# clock.net
KiCad netlist of a schematic drawn in EAGLE
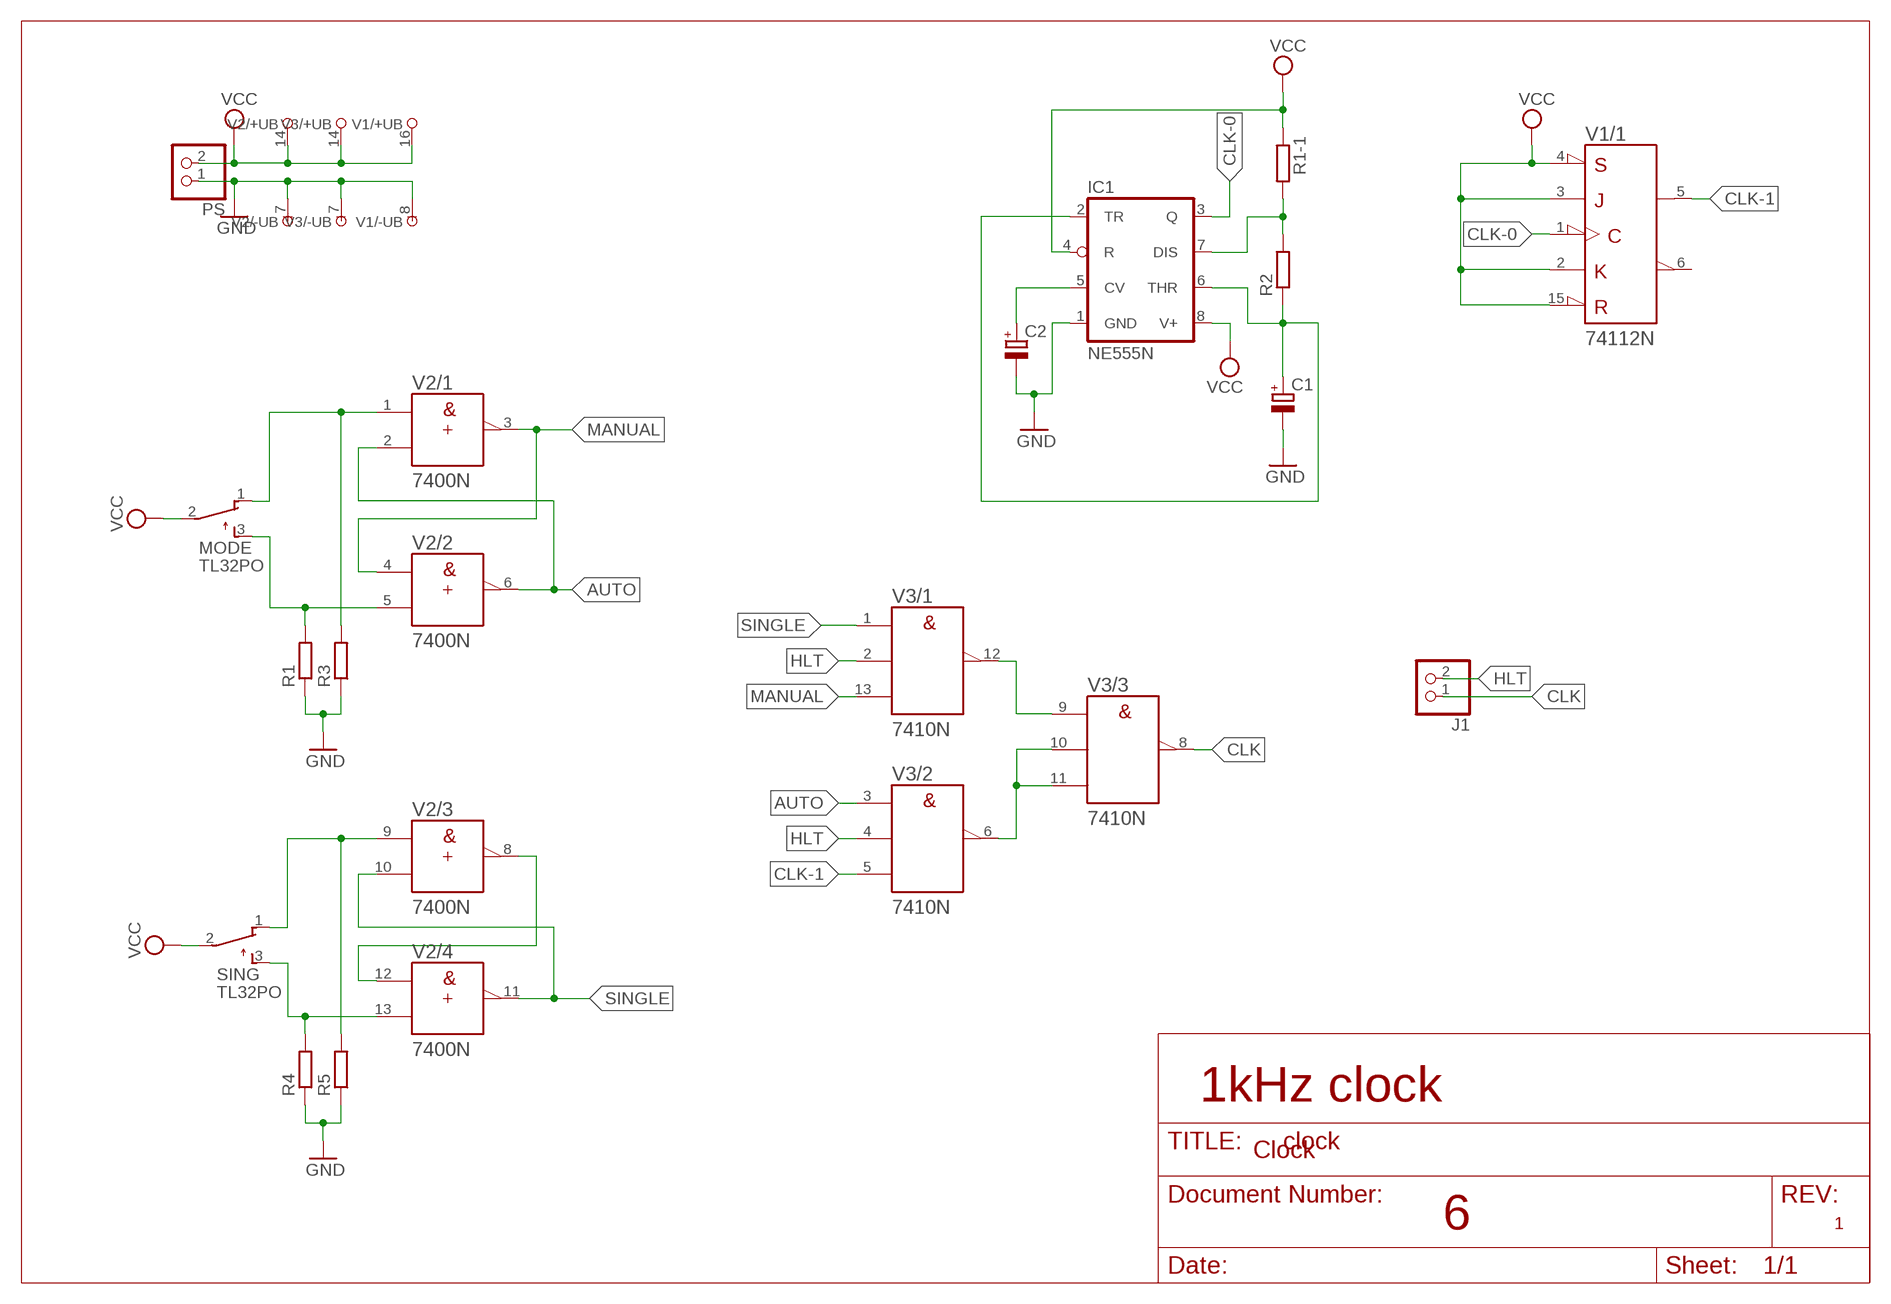
[diagram p0: schematic, sheet 1]

(export (version "E")
  (design (tool "Eeschema 10.0.6"))
  (components
    (comp (ref "C1")
      (value "CPOL-EUE2.5-6")
      (footprint "eagle-import:E2,5-6")
      (libsource (lib "eagle-import") (part "CPOL-EUE2.5-6"))
    )
    (comp (ref "C2")
      (value "CPOL-EUE2.5-6")
      (footprint "eagle-import:E2,5-6")
      (libsource (lib "eagle-import") (part "CPOL-EUE2.5-6"))
    )
    (comp (ref "IC1")
      (value "NE555N")
      (footprint "eagle-import:DIL08")
      (libsource (lib "eagle-import") (part "555NNE"))
    )
    (comp (ref "J1")
      (value "PINHD-1X2")
      (footprint "eagle-import:1X02")
      (libsource (lib "eagle-import") (part "PINHD-1X2"))
    )
    (comp (ref "MODE")
      (value "TL32PO")
      (footprint "eagle-import:TL3XPO")
      (libsource (lib "eagle-import") (part "TL32PO"))
    )
    (comp (ref "PS")
      (value "PINHD-1X2")
      (footprint "eagle-import:1X02")
      (libsource (lib "eagle-import") (part "PINHD-1X2"))
    )
    (comp (ref "R1")
      (value "R-EU_0204/7")
      (footprint "eagle-import:0204_7")
      (libsource (lib "eagle-import") (part "R-EU_0204/7"))
    )
    (comp (ref "R1-1")
      (value "R-EU_0207/10")
      (footprint "eagle-import:0207_10")
      (libsource (lib "eagle-import") (part "R-EU_0207/10"))
    )
    (comp (ref "R2")
      (value "R-EU_0207/10")
      (footprint "eagle-import:0207_10")
      (libsource (lib "eagle-import") (part "R-EU_0207/10"))
    )
    (comp (ref "R3")
      (value "R-EU_0204/7")
      (footprint "eagle-import:0204_7")
      (libsource (lib "eagle-import") (part "R-EU_0204/7"))
    )
    (comp (ref "R4")
      (value "R-EU_0204/7")
      (footprint "eagle-import:0204_7")
      (libsource (lib "eagle-import") (part "R-EU_0204/7"))
    )
    (comp (ref "R5")
      (value "R-EU_0204/7")
      (footprint "eagle-import:0204_7")
      (libsource (lib "eagle-import") (part "R-EU_0204/7"))
    )
    (comp (ref "SING")
      (value "TL32PO")
      (footprint "eagle-import:TL3XPO")
      (libsource (lib "eagle-import") (part "TL32PO"))
    )
    (comp (ref "V1")
      (value "74112N")
      (footprint "eagle-import:DIL16")
      (libsource (lib "eagle-import") (part "74112N"))
    )
    (comp (ref "V2")
      (value "7400N")
      (footprint "eagle-import:DIL14")
      (libsource (lib "eagle-import") (part "7400N"))
    )
    (comp (ref "V3")
      (value "7410N")
      (footprint "eagle-import:DIL14")
      (libsource (lib "eagle-import") (part "7410N"))
    )
  )
  (nets
    (net (code "1") (name "AUTO") (class "Default")
      (node (ref "V2") (pin "2") (pinfunction "B_2") (pintype "input"))
      (node (ref "V2") (pin "6") (pinfunction "Y_6") (pintype "output"))
      (node (ref "V3") (pin "3") (pinfunction "A_3") (pintype "input"))
    )
    (net (code "2") (name "CLK") (class "Default")
      (node (ref "J1") (pin "1") (pinfunction "1_1") (pintype "passive"))
      (node (ref "V3") (pin "8") (pinfunction "Y_8") (pintype "output"))
    )
    (net (code "3") (name "CLK-0") (class "Default")
      (node (ref "IC1") (pin "3") (pinfunction "Q_3") (pintype "output"))
      (node (ref "V1") (pin "1") (pinfunction "CLK_1") (pintype "input"))
    )
    (net (code "4") (name "CLK-1") (class "Default")
      (node (ref "V1") (pin "5") (pinfunction "Q_5") (pintype "output"))
      (node (ref "V3") (pin "5") (pinfunction "C_5") (pintype "input"))
    )
    (net (code "5") (name "GND") (class "Default")
      (node (ref "C1") (pin "-") (pinfunction "-_-") (pintype "passive"))
      (node (ref "C2") (pin "-") (pinfunction "-_-") (pintype "passive"))
      (node (ref "IC1") (pin "1") (pinfunction "GND_1") (pintype "power_in"))
      (node (ref "PS") (pin "1") (pinfunction "1_1") (pintype "passive"))
      (node (ref "R1") (pin "1") (pinfunction "1_1") (pintype "passive"))
      (node (ref "R3") (pin "1") (pinfunction "1_1") (pintype "passive"))
      (node (ref "R4") (pin "1") (pinfunction "1_1") (pintype "passive"))
      (node (ref "R5") (pin "1") (pinfunction "1_1") (pintype "passive"))
      (node (ref "V1") (pin "8") (pinfunction "-UB_8") (pintype "power_in"))
      (node (ref "V2") (pin "7") (pinfunction "-UB_7") (pintype "power_in"))
      (node (ref "V3") (pin "7") (pinfunction "-UB_7") (pintype "power_in"))
    )
    (net (code "6") (name "HLT") (class "Default")
      (node (ref "J1") (pin "2") (pinfunction "2_2") (pintype "passive"))
      (node (ref "V3") (pin "2") (pinfunction "B_2") (pintype "input"))
      (node (ref "V3") (pin "4") (pinfunction "B_4") (pintype "input"))
    )
    (net (code "7") (name "MANUAL") (class "Default")
      (node (ref "V2") (pin "3") (pinfunction "Y_3") (pintype "output"))
      (node (ref "V2") (pin "4") (pinfunction "A_4") (pintype "input"))
      (node (ref "V3") (pin "13") (pinfunction "C_13") (pintype "input"))
    )
    (net (code "8") (name "Net-(IC1-CV)") (class "Default")
      (node (ref "C2") (pin "+") (pinfunction "+_+") (pintype "passive"))
      (node (ref "IC1") (pin "5") (pinfunction "CV_5") (pintype "input"))
    )
    (net (code "9") (name "Net-(IC1-DIS)") (class "Default")
      (node (ref "IC1") (pin "7") (pinfunction "DIS_7") (pintype "input"))
      (node (ref "R1-1") (pin "2") (pinfunction "2_2") (pintype "passive"))
      (node (ref "R2") (pin "2") (pinfunction "2_2") (pintype "passive"))
    )
    (net (code "10") (name "Net-(IC1-THR)") (class "Default")
      (node (ref "C1") (pin "+") (pinfunction "+_+") (pintype "passive"))
      (node (ref "IC1") (pin "2") (pinfunction "TR_2") (pintype "input"))
      (node (ref "IC1") (pin "6") (pinfunction "THR_6") (pintype "input"))
      (node (ref "R2") (pin "1") (pinfunction "1_1") (pintype "passive"))
    )
    (net (code "11") (name "Net-(MODE-O)") (class "Default")
      (node (ref "MODE") (pin "1") (pinfunction "O_1") (pintype "passive"))
      (node (ref "R3") (pin "2") (pinfunction "2_2") (pintype "passive"))
      (node (ref "V2") (pin "1") (pinfunction "A_1") (pintype "input"))
    )
    (net (code "12") (name "Net-(MODE-S)") (class "Default")
      (node (ref "MODE") (pin "3") (pinfunction "S_3") (pintype "passive"))
      (node (ref "R1") (pin "2") (pinfunction "2_2") (pintype "passive"))
      (node (ref "V2") (pin "5") (pinfunction "B_5") (pintype "input"))
    )
    (net (code "13") (name "Net-(SING-O)") (class "Default")
      (node (ref "R5") (pin "2") (pinfunction "2_2") (pintype "passive"))
      (node (ref "SING") (pin "1") (pinfunction "O_1") (pintype "passive"))
      (node (ref "V2") (pin "9") (pinfunction "A_9") (pintype "input"))
    )
    (net (code "14") (name "Net-(SING-S)") (class "Default")
      (node (ref "R4") (pin "2") (pinfunction "2_2") (pintype "passive"))
      (node (ref "SING") (pin "3") (pinfunction "S_3") (pintype "passive"))
      (node (ref "V2") (pin "13") (pinfunction "B_13") (pintype "input"))
    )
    (net (code "15") (name "Net-(V2E-Y)") (class "Default")
      (node (ref "V2") (pin "12") (pinfunction "A_12") (pintype "input"))
      (node (ref "V2") (pin "8") (pinfunction "Y_8") (pintype "output"))
    )
    (net (code "16") (name "Net-(V3C-Y)") (class "Default")
      (node (ref "V3") (pin "12") (pinfunction "Y_12") (pintype "output"))
      (node (ref "V3") (pin "9") (pinfunction "A_9") (pintype "input"))
    )
    (net (code "17") (name "Net-(V3D-Y)") (class "Default")
      (node (ref "V3") (pin "10") (pinfunction "B_10") (pintype "input"))
      (node (ref "V3") (pin "11") (pinfunction "C_11") (pintype "input"))
      (node (ref "V3") (pin "6") (pinfunction "Y_6") (pintype "output"))
    )
    (net (code "18") (name "SINGLE") (class "Default")
      (node (ref "V2") (pin "10") (pinfunction "B_10") (pintype "input"))
      (node (ref "V2") (pin "11") (pinfunction "Y_11") (pintype "output"))
      (node (ref "V3") (pin "1") (pinfunction "A_1") (pintype "input"))
    )
    (net (code "19") (name "VCC") (class "Default")
      (node (ref "IC1") (pin "4") (pinfunction "R_4") (pintype "input"))
      (node (ref "IC1") (pin "8") (pinfunction "V+_8") (pintype "power_in"))
      (node (ref "MODE") (pin "2") (pinfunction "P_2") (pintype "passive"))
      (node (ref "PS") (pin "2") (pinfunction "2_2") (pintype "passive"))
      (node (ref "R1-1") (pin "1") (pinfunction "1_1") (pintype "passive"))
      (node (ref "SING") (pin "2") (pinfunction "P_2") (pintype "passive"))
      (node (ref "V1") (pin "15") (pinfunction "~{CLR}_15") (pintype "input"))
      (node (ref "V1") (pin "16") (pinfunction "+UB_16") (pintype "power_in"))
      (node (ref "V1") (pin "2") (pinfunction "K_2") (pintype "input"))
      (node (ref "V1") (pin "3") (pinfunction "J_3") (pintype "input"))
      (node (ref "V1") (pin "4") (pinfunction "~{PRE}_4") (pintype "input"))
      (node (ref "V2") (pin "14") (pinfunction "+UB_14") (pintype "power_in"))
      (node (ref "V3") (pin "14") (pinfunction "+UB_14") (pintype "power_in"))
    )
    (net (code "20") (name "unconnected-(V1C-~{Q}-Pad6)") (class "Default")
      (node (ref "V1") (pin "6") (pinfunction "~{Q}_6") (pintype "output"))
    )
  )
)
